# kontrol.net
KiCad netlist of a schematic drawn in EAGLE
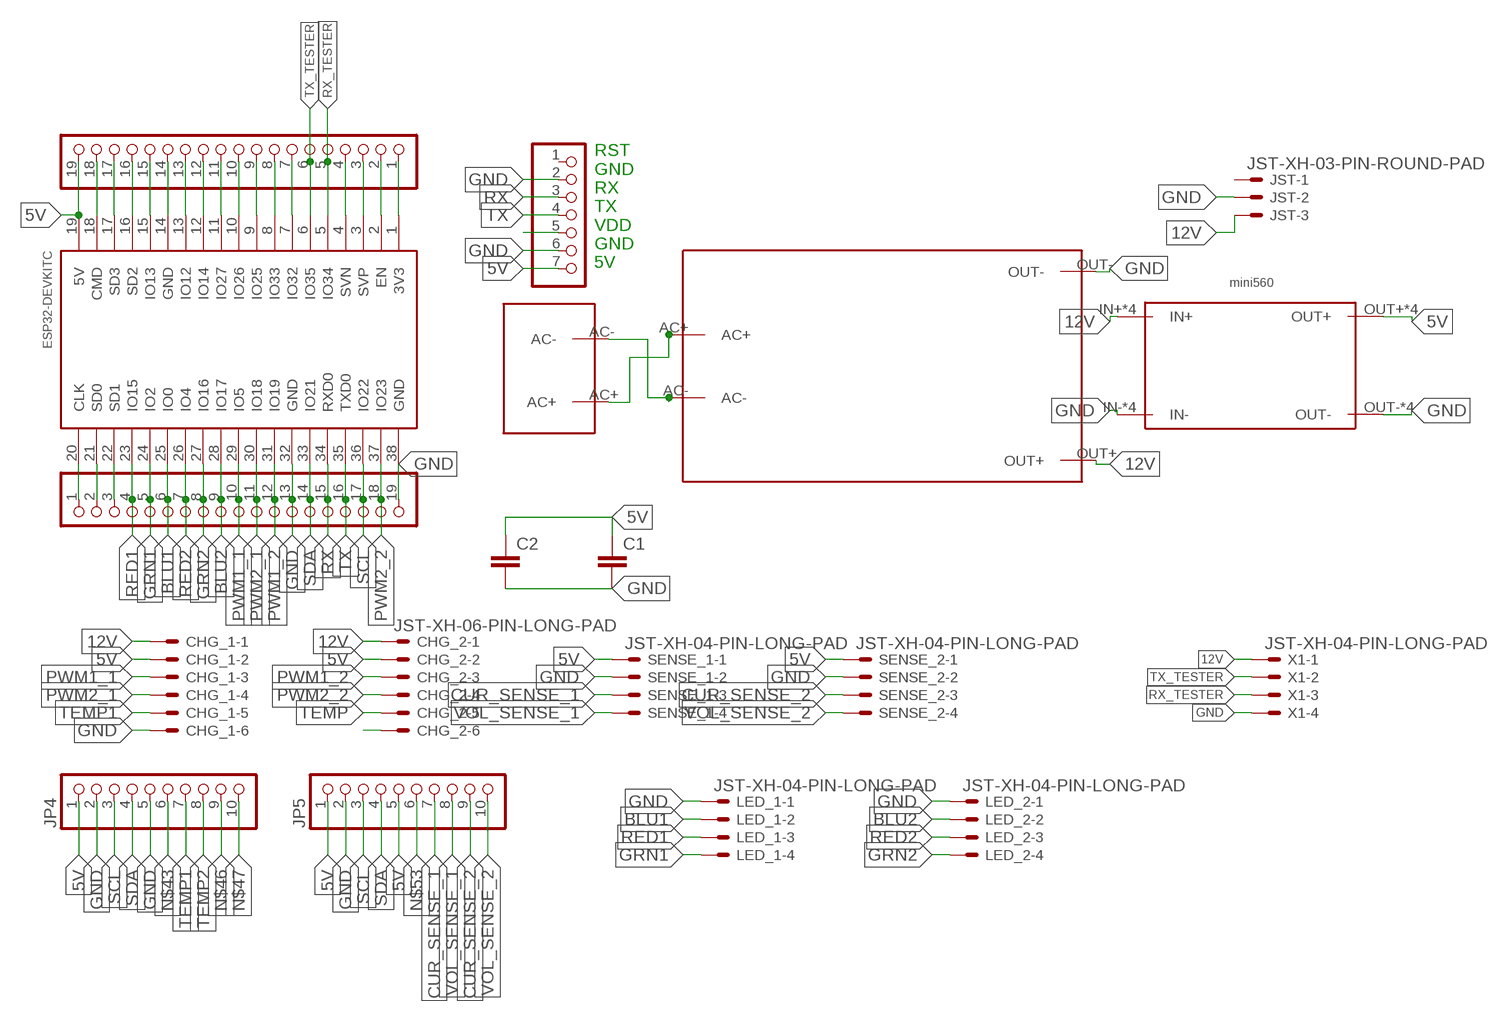
[diagram p0: schematic, sheet 1]

(export (version "E")
  (design (tool "Eeschema 10.0.6"))
  (components
    (comp (ref "AC_CONNECTOR1")
      (value "AC_CONNECTOR")
      (footprint "eagle-import:AC_CONNECTOR")
      (libsource (lib "eagle-import") (part "AC_CONNECTOR"))
    )
    (comp (ref "C1")
      (value "C2.5/5")
      (footprint "eagle-import:C2.5-5")
      (libsource (lib "eagle-import") (part "C2.5/5"))
    )
    (comp (ref "C2")
      (value "C2.5/6")
      (footprint "eagle-import:C2.5-6")
      (libsource (lib "eagle-import") (part "C2.5/6"))
    )
    (comp (ref "CHG_1")
      (value "JST-XH-06-PIN-LONG-PAD")
      (footprint "eagle-import:JST-XH-06-PACKAGE-LONG-PAD")
      (libsource (lib "eagle-import") (part "JST-XH-06-PIN-LONG-PAD"))
    )
    (comp (ref "CHG_2")
      (value "JST-XH-06-PIN-LONG-PAD")
      (footprint "eagle-import:JST-XH-06-PACKAGE-LONG-PAD")
      (libsource (lib "eagle-import") (part "JST-XH-06-PIN-LONG-PAD"))
    )
    (comp (ref "HI_LINK1")
      (value "HI_LINK")
      (footprint "eagle-import:HI_LINK")
      (libsource (lib "eagle-import") (part "HI_LINK"))
    )
    (comp (ref "JP1")
      (value "PINHD-1X7")
      (footprint "eagle-import:1X07")
      (libsource (lib "eagle-import") (part "PINHD-1X7"))
    )
    (comp (ref "JP2")
      (value "PINHD-1X19")
      (footprint "eagle-import:1X19")
      (libsource (lib "eagle-import") (part "PINHD-1X19"))
    )
    (comp (ref "JP3")
      (value "PINHD-1X19")
      (footprint "eagle-import:1X19")
      (libsource (lib "eagle-import") (part "PINHD-1X19"))
    )
    (comp (ref "JP4")
      (value "PINHD-1X10")
      (footprint "eagle-import:1X10")
      (libsource (lib "eagle-import") (part "PINHD-1X10"))
    )
    (comp (ref "JP5")
      (value "PINHD-1X10")
      (footprint "eagle-import:1X10")
      (libsource (lib "eagle-import") (part "PINHD-1X10"))
    )
    (comp (ref "JST")
      (value "JST-XH-03-PIN-ROUND-PAD")
      (footprint "eagle-import:JST-XH-03-PACKAGE-ROUND-PAD")
      (libsource (lib "eagle-import") (part "JST-XH-03-PIN-ROUND-PAD"))
    )
    (comp (ref "LED_1")
      (value "JST-XH-04-PIN-LONG-PAD")
      (footprint "eagle-import:JST-XH-04-PACKAGE-LONG-PAD")
      (libsource (lib "eagle-import") (part "JST-XH-04-PIN-LONG-PAD"))
    )
    (comp (ref "LED_2")
      (value "JST-XH-04-PIN-LONG-PAD")
      (footprint "eagle-import:JST-XH-04-PACKAGE-LONG-PAD")
      (libsource (lib "eagle-import") (part "JST-XH-04-PIN-LONG-PAD"))
    )
    (comp (ref "MINI1")
      (value "MINI560")
      (footprint "eagle-import:MINI560")
      (libsource (lib "eagle-import") (part "MINI560"))
    )
    (comp (ref "SENSE_1")
      (value "JST-XH-04-PIN-LONG-PAD")
      (footprint "eagle-import:JST-XH-04-PACKAGE-LONG-PAD")
      (libsource (lib "eagle-import") (part "JST-XH-04-PIN-LONG-PAD"))
    )
    (comp (ref "SENSE_2")
      (value "JST-XH-04-PIN-LONG-PAD")
      (footprint "eagle-import:JST-XH-04-PACKAGE-LONG-PAD")
      (libsource (lib "eagle-import") (part "JST-XH-04-PIN-LONG-PAD"))
    )
    (comp (ref "U$1")
      (value "ESP32DEVKITC")
      (footprint "eagle-import:ESP32-DEVKITC")
      (libsource (lib "eagle-import") (part "ESP32DEVKITC"))
    )
    (comp (ref "X1")
      (value "JST-XH-04-PIN-LONG-PAD")
      (footprint "eagle-import:JST-XH-04-PACKAGE-LONG-PAD")
      (libsource (lib "eagle-import") (part "Rembrandt Electronics - JST XH Connectors v1-0_JST-XH-04-PIN-LONG-PAD"))
    )
  )
  (nets
    (net (code "1") (name "5V") (class "Default")
      (node (ref "C1") (pin "1") (pinfunction "1_1") (pintype "passive"))
      (node (ref "C2") (pin "1") (pinfunction "1_1") (pintype "passive"))
      (node (ref "CHG_1") (pin "2") (pinfunction "S_2") (pintype "passive"))
      (node (ref "CHG_2") (pin "2") (pinfunction "S_2") (pintype "passive"))
      (node (ref "JP1") (pin "7") (pinfunction "7_7") (pintype "passive"))
      (node (ref "JP3") (pin "19") (pinfunction "19_19") (pintype "passive"))
      (node (ref "JP4") (pin "1") (pinfunction "1_1") (pintype "passive"))
      (node (ref "JP5") (pin "1") (pinfunction "1_1") (pintype "passive"))
      (node (ref "JP5") (pin "5") (pinfunction "5_5") (pintype "passive"))
      (node (ref "MINI1") (pin "OUT+") (pinfunction "OUT+_OUT+") (pintype "bidirectional"))
      (node (ref "MINI1") (pin "OUT+1") (pinfunction "OUT+_OUT+1") (pintype "bidirectional"))
      (node (ref "MINI1") (pin "OUT+2") (pinfunction "OUT+_OUT+2") (pintype "bidirectional"))
      (node (ref "MINI1") (pin "OUT+3") (pinfunction "OUT+_OUT+3") (pintype "bidirectional"))
      (node (ref "SENSE_1") (pin "1") (pinfunction "S_1") (pintype "passive"))
      (node (ref "SENSE_2") (pin "1") (pinfunction "S_1") (pintype "passive"))
      (node (ref "U$1") (pin "19") (pinfunction "5V_19") (pintype "bidirectional"))
    )
    (net (code "2") (name "12V") (class "Default")
      (node (ref "CHG_1") (pin "1") (pinfunction "S_1") (pintype "passive"))
      (node (ref "CHG_2") (pin "1") (pinfunction "S_1") (pintype "passive"))
      (node (ref "HI_LINK1") (pin "OUT+") (pinfunction "OUT+_OUT+") (pintype "bidirectional"))
      (node (ref "JST") (pin "3") (pinfunction "S_3") (pintype "passive"))
      (node (ref "MINI1") (pin "IN+") (pinfunction "IN+_IN+") (pintype "bidirectional"))
      (node (ref "MINI1") (pin "IN+1") (pinfunction "IN+_IN+1") (pintype "bidirectional"))
      (node (ref "MINI1") (pin "IN+2") (pinfunction "IN+_IN+2") (pintype "bidirectional"))
      (node (ref "MINI1") (pin "IN+3") (pinfunction "IN+_IN+3") (pintype "bidirectional"))
      (node (ref "X1") (pin "1") (pinfunction "S_1") (pintype "passive"))
    )
    (net (code "3") (name "BLU1") (class "Default")
      (node (ref "JP2") (pin "6") (pinfunction "6_6") (pintype "passive"))
      (node (ref "LED_1") (pin "2") (pinfunction "S_2") (pintype "passive"))
      (node (ref "U$1") (pin "25") (pinfunction "IO0_25") (pintype "bidirectional"))
    )
    (net (code "4") (name "BLU2") (class "Default")
      (node (ref "JP2") (pin "9") (pinfunction "9_9") (pintype "passive"))
      (node (ref "LED_2") (pin "2") (pinfunction "S_2") (pintype "passive"))
      (node (ref "U$1") (pin "28") (pinfunction "IO17_28") (pintype "bidirectional"))
    )
    (net (code "5") (name "CUR_SENSE_1") (class "Default")
      (node (ref "JP5") (pin "7") (pinfunction "7_7") (pintype "passive"))
      (node (ref "SENSE_1") (pin "3") (pinfunction "S_3") (pintype "passive"))
    )
    (net (code "6") (name "CUR_SENSE_2") (class "Default")
      (node (ref "JP5") (pin "9") (pinfunction "9_9") (pintype "passive"))
      (node (ref "SENSE_2") (pin "3") (pinfunction "S_3") (pintype "passive"))
    )
    (net (code "7") (name "GND") (class "Default")
      (node (ref "C1") (pin "2") (pinfunction "2_2") (pintype "passive"))
      (node (ref "C2") (pin "2") (pinfunction "2_2") (pintype "passive"))
      (node (ref "CHG_1") (pin "6") (pinfunction "S_6") (pintype "passive"))
      (node (ref "CHG_2") (pin "6") (pinfunction "S_6") (pintype "passive"))
      (node (ref "HI_LINK1") (pin "OUT-") (pinfunction "OUT-_OUT-") (pintype "bidirectional"))
      (node (ref "JP1") (pin "2") (pinfunction "2_2") (pintype "passive"))
      (node (ref "JP1") (pin "6") (pinfunction "6_6") (pintype "passive"))
      (node (ref "JP2") (pin "13") (pinfunction "13_13") (pintype "passive"))
      (node (ref "JP2") (pin "19") (pinfunction "19_19") (pintype "passive"))
      (node (ref "JP4") (pin "2") (pinfunction "2_2") (pintype "passive"))
      (node (ref "JP4") (pin "5") (pinfunction "5_5") (pintype "passive"))
      (node (ref "JP5") (pin "2") (pinfunction "2_2") (pintype "passive"))
      (node (ref "JST") (pin "2") (pinfunction "S_2") (pintype "passive"))
      (node (ref "LED_1") (pin "1") (pinfunction "S_1") (pintype "passive"))
      (node (ref "LED_2") (pin "1") (pinfunction "S_1") (pintype "passive"))
      (node (ref "MINI1") (pin "IN-") (pinfunction "IN-_IN-") (pintype "bidirectional"))
      (node (ref "MINI1") (pin "IN-1") (pinfunction "IN-_IN-1") (pintype "bidirectional"))
      (node (ref "MINI1") (pin "IN-2") (pinfunction "IN-_IN-2") (pintype "bidirectional"))
      (node (ref "MINI1") (pin "IN-3") (pinfunction "IN-_IN-3") (pintype "bidirectional"))
      (node (ref "MINI1") (pin "OUT-") (pinfunction "OUT-_OUT-") (pintype "bidirectional"))
      (node (ref "MINI1") (pin "OUT-1") (pinfunction "OUT-_OUT-1") (pintype "bidirectional"))
      (node (ref "MINI1") (pin "OUT-2") (pinfunction "OUT-_OUT-2") (pintype "bidirectional"))
      (node (ref "MINI1") (pin "OUT-3") (pinfunction "OUT-_OUT-3") (pintype "bidirectional"))
      (node (ref "SENSE_1") (pin "2") (pinfunction "S_2") (pintype "passive"))
      (node (ref "SENSE_2") (pin "2") (pinfunction "S_2") (pintype "passive"))
      (node (ref "U$1") (pin "32") (pinfunction "GND_32") (pintype "bidirectional"))
      (node (ref "U$1") (pin "38") (pinfunction "GND_38") (pintype "bidirectional"))
      (node (ref "X1") (pin "4") (pinfunction "S_4") (pintype "passive"))
    )
    (net (code "8") (name "GRN1") (class "Default")
      (node (ref "JP2") (pin "5") (pinfunction "5_5") (pintype "passive"))
      (node (ref "LED_1") (pin "4") (pinfunction "S_4") (pintype "passive"))
      (node (ref "U$1") (pin "24") (pinfunction "IO2_24") (pintype "bidirectional"))
    )
    (net (code "9") (name "GRN2") (class "Default")
      (node (ref "JP2") (pin "8") (pinfunction "8_8") (pintype "passive"))
      (node (ref "LED_2") (pin "4") (pinfunction "S_4") (pintype "passive"))
      (node (ref "U$1") (pin "27") (pinfunction "IO16_27") (pintype "bidirectional"))
    )
    (net (code "10") (name "N$43") (class "Default")
      (node (ref "JP4") (pin "6") (pinfunction "6_6") (pintype "passive"))
    )
    (net (code "11") (name "N$46") (class "Default")
      (node (ref "JP4") (pin "9") (pinfunction "9_9") (pintype "passive"))
    )
    (net (code "12") (name "N$47") (class "Default")
      (node (ref "JP4") (pin "10") (pinfunction "10_10") (pintype "passive"))
    )
    (net (code "13") (name "N$53") (class "Default")
      (node (ref "JP5") (pin "6") (pinfunction "6_6") (pintype "passive"))
    )
    (net (code "14") (name "Net-(AC_CONNECTOR1-PadAC+)") (class "Default")
      (node (ref "AC_CONNECTOR1") (pin "AC+") (pinfunction "AC+_AC+") (pintype "bidirectional"))
      (node (ref "HI_LINK1") (pin "AC+") (pinfunction "AC+_AC+") (pintype "bidirectional"))
    )
    (net (code "15") (name "Net-(AC_CONNECTOR1-PadAC-)") (class "Default")
      (node (ref "AC_CONNECTOR1") (pin "AC-") (pinfunction "AC-_AC-") (pintype "bidirectional"))
      (node (ref "HI_LINK1") (pin "AC-") (pinfunction "AC-_AC-") (pintype "bidirectional"))
    )
    (net (code "16") (name "Net-(JP3-Pad14)") (class "Default")
      (node (ref "JP3") (pin "14") (pinfunction "14_14") (pintype "passive"))
      (node (ref "U$1") (pin "14") (pinfunction "GND_14") (pintype "bidirectional"))
    )
    (net (code "17") (name "Net-(U$1-3V3)") (class "Default")
      (node (ref "JP3") (pin "1") (pinfunction "1_1") (pintype "passive"))
      (node (ref "U$1") (pin "1") (pinfunction "3V3_1") (pintype "bidirectional"))
    )
    (net (code "18") (name "Net-(U$1-CLK)") (class "Default")
      (node (ref "JP2") (pin "1") (pinfunction "1_1") (pintype "passive"))
      (node (ref "U$1") (pin "20") (pinfunction "CLK_20") (pintype "bidirectional"))
    )
    (net (code "19") (name "Net-(U$1-CMD)") (class "Default")
      (node (ref "JP3") (pin "18") (pinfunction "18_18") (pintype "passive"))
      (node (ref "U$1") (pin "18") (pinfunction "CMD_18") (pintype "bidirectional"))
    )
    (net (code "20") (name "Net-(U$1-EN)") (class "Default")
      (node (ref "JP3") (pin "2") (pinfunction "2_2") (pintype "passive"))
      (node (ref "U$1") (pin "2") (pinfunction "EN_2") (pintype "bidirectional"))
    )
    (net (code "21") (name "Net-(U$1-IO12)") (class "Default")
      (node (ref "JP3") (pin "13") (pinfunction "13_13") (pintype "passive"))
      (node (ref "U$1") (pin "13") (pinfunction "IO12_13") (pintype "bidirectional"))
    )
    (net (code "22") (name "Net-(U$1-IO13)") (class "Default")
      (node (ref "JP3") (pin "15") (pinfunction "15_15") (pintype "passive"))
      (node (ref "U$1") (pin "15") (pinfunction "IO13_15") (pintype "bidirectional"))
    )
    (net (code "23") (name "Net-(U$1-IO14)") (class "Default")
      (node (ref "JP3") (pin "12") (pinfunction "12_12") (pintype "passive"))
      (node (ref "U$1") (pin "12") (pinfunction "IO14_12") (pintype "bidirectional"))
    )
    (net (code "24") (name "Net-(U$1-IO25)") (class "Default")
      (node (ref "JP3") (pin "9") (pinfunction "9_9") (pintype "passive"))
      (node (ref "U$1") (pin "9") (pinfunction "IO25_9") (pintype "bidirectional"))
    )
    (net (code "25") (name "Net-(U$1-IO26)") (class "Default")
      (node (ref "JP3") (pin "10") (pinfunction "10_10") (pintype "passive"))
      (node (ref "U$1") (pin "10") (pinfunction "IO26_10") (pintype "bidirectional"))
    )
    (net (code "26") (name "Net-(U$1-IO27)") (class "Default")
      (node (ref "JP3") (pin "11") (pinfunction "11_11") (pintype "passive"))
      (node (ref "U$1") (pin "11") (pinfunction "IO27_11") (pintype "bidirectional"))
    )
    (net (code "27") (name "Net-(U$1-IO32)") (class "Default")
      (node (ref "JP3") (pin "7") (pinfunction "7_7") (pintype "passive"))
      (node (ref "U$1") (pin "7") (pinfunction "IO32_7") (pintype "bidirectional"))
    )
    (net (code "28") (name "Net-(U$1-IO33)") (class "Default")
      (node (ref "JP3") (pin "8") (pinfunction "8_8") (pintype "passive"))
      (node (ref "U$1") (pin "8") (pinfunction "IO33_8") (pintype "bidirectional"))
    )
    (net (code "29") (name "Net-(U$1-SD0)") (class "Default")
      (node (ref "JP2") (pin "2") (pinfunction "2_2") (pintype "passive"))
      (node (ref "U$1") (pin "21") (pinfunction "SD0_21") (pintype "bidirectional"))
    )
    (net (code "30") (name "Net-(U$1-SD1)") (class "Default")
      (node (ref "JP2") (pin "3") (pinfunction "3_3") (pintype "passive"))
      (node (ref "U$1") (pin "22") (pinfunction "SD1_22") (pintype "bidirectional"))
    )
    (net (code "31") (name "Net-(U$1-SD2)") (class "Default")
      (node (ref "JP3") (pin "16") (pinfunction "16_16") (pintype "passive"))
      (node (ref "U$1") (pin "16") (pinfunction "SD2_16") (pintype "bidirectional"))
    )
    (net (code "32") (name "Net-(U$1-SD3)") (class "Default")
      (node (ref "JP3") (pin "17") (pinfunction "17_17") (pintype "passive"))
      (node (ref "U$1") (pin "17") (pinfunction "SD3_17") (pintype "bidirectional"))
    )
    (net (code "33") (name "Net-(U$1-SVN)") (class "Default")
      (node (ref "JP3") (pin "4") (pinfunction "4_4") (pintype "passive"))
      (node (ref "U$1") (pin "4") (pinfunction "SVN_4") (pintype "bidirectional"))
    )
    (net (code "34") (name "Net-(U$1-SVP)") (class "Default")
      (node (ref "JP3") (pin "3") (pinfunction "3_3") (pintype "passive"))
      (node (ref "U$1") (pin "3") (pinfunction "SVP_3") (pintype "bidirectional"))
    )
    (net (code "35") (name "PWM1_1") (class "Default")
      (node (ref "CHG_1") (pin "3") (pinfunction "S_3") (pintype "passive"))
      (node (ref "JP2") (pin "10") (pinfunction "10_10") (pintype "passive"))
      (node (ref "U$1") (pin "29") (pinfunction "IO5_29") (pintype "bidirectional"))
    )
    (net (code "36") (name "PWM1_2") (class "Default")
      (node (ref "CHG_2") (pin "3") (pinfunction "S_3") (pintype "passive"))
      (node (ref "JP2") (pin "12") (pinfunction "12_12") (pintype "passive"))
      (node (ref "U$1") (pin "31") (pinfunction "IO19_31") (pintype "bidirectional"))
    )
    (net (code "37") (name "PWM2_1") (class "Default")
      (node (ref "CHG_1") (pin "4") (pinfunction "S_4") (pintype "passive"))
      (node (ref "JP2") (pin "11") (pinfunction "11_11") (pintype "passive"))
      (node (ref "U$1") (pin "30") (pinfunction "IO18_30") (pintype "bidirectional"))
    )
    (net (code "38") (name "PWM2_2") (class "Default")
      (node (ref "CHG_2") (pin "4") (pinfunction "S_4") (pintype "passive"))
      (node (ref "JP2") (pin "18") (pinfunction "18_18") (pintype "passive"))
      (node (ref "U$1") (pin "37") (pinfunction "IO23_37") (pintype "bidirectional"))
    )
    (net (code "39") (name "RED1") (class "Default")
      (node (ref "JP2") (pin "4") (pinfunction "4_4") (pintype "passive"))
      (node (ref "LED_1") (pin "3") (pinfunction "S_3") (pintype "passive"))
      (node (ref "U$1") (pin "23") (pinfunction "IO15_23") (pintype "bidirectional"))
    )
    (net (code "40") (name "RED2") (class "Default")
      (node (ref "JP2") (pin "7") (pinfunction "7_7") (pintype "passive"))
      (node (ref "LED_2") (pin "3") (pinfunction "S_3") (pintype "passive"))
      (node (ref "U$1") (pin "26") (pinfunction "IO4_26") (pintype "bidirectional"))
    )
    (net (code "41") (name "RX") (class "Default")
      (node (ref "JP1") (pin "3") (pinfunction "3_3") (pintype "passive"))
      (node (ref "JP2") (pin "15") (pinfunction "15_15") (pintype "passive"))
      (node (ref "U$1") (pin "34") (pinfunction "RXD0_34") (pintype "bidirectional"))
    )
    (net (code "42") (name "RX_TESTER") (class "Default")
      (node (ref "JP3") (pin "5") (pinfunction "5_5") (pintype "passive"))
      (node (ref "U$1") (pin "5") (pinfunction "IO34_5") (pintype "bidirectional"))
      (node (ref "X1") (pin "3") (pinfunction "S_3") (pintype "passive"))
    )
    (net (code "43") (name "SCL") (class "Default")
      (node (ref "JP2") (pin "17") (pinfunction "17_17") (pintype "passive"))
      (node (ref "JP4") (pin "3") (pinfunction "3_3") (pintype "passive"))
      (node (ref "JP5") (pin "3") (pinfunction "3_3") (pintype "passive"))
      (node (ref "U$1") (pin "36") (pinfunction "IO22_36") (pintype "bidirectional"))
    )
    (net (code "44") (name "SDA") (class "Default")
      (node (ref "JP2") (pin "14") (pinfunction "14_14") (pintype "passive"))
      (node (ref "JP4") (pin "4") (pinfunction "4_4") (pintype "passive"))
      (node (ref "JP5") (pin "4") (pinfunction "4_4") (pintype "passive"))
      (node (ref "U$1") (pin "33") (pinfunction "IO21_33") (pintype "bidirectional"))
    )
    (net (code "45") (name "TEMP") (class "Default")
      (node (ref "CHG_2") (pin "5") (pinfunction "S_5") (pintype "passive"))
    )
    (net (code "46") (name "TEMP1") (class "Default")
      (node (ref "CHG_1") (pin "5") (pinfunction "S_5") (pintype "passive"))
      (node (ref "JP4") (pin "7") (pinfunction "7_7") (pintype "passive"))
    )
    (net (code "47") (name "TEMP2") (class "Default")
      (node (ref "JP4") (pin "8") (pinfunction "8_8") (pintype "passive"))
    )
    (net (code "48") (name "TX") (class "Default")
      (node (ref "JP1") (pin "4") (pinfunction "4_4") (pintype "passive"))
      (node (ref "JP2") (pin "16") (pinfunction "16_16") (pintype "passive"))
      (node (ref "U$1") (pin "35") (pinfunction "TXD0_35") (pintype "bidirectional"))
    )
    (net (code "49") (name "TX_TESTER") (class "Default")
      (node (ref "JP3") (pin "6") (pinfunction "6_6") (pintype "passive"))
      (node (ref "U$1") (pin "6") (pinfunction "IO35_6") (pintype "bidirectional"))
      (node (ref "X1") (pin "2") (pinfunction "S_2") (pintype "passive"))
    )
    (net (code "50") (name "VOL_SENSE_1") (class "Default")
      (node (ref "JP5") (pin "8") (pinfunction "8_8") (pintype "passive"))
      (node (ref "SENSE_1") (pin "4") (pinfunction "S_4") (pintype "passive"))
    )
    (net (code "51") (name "VOL_SENSE_2") (class "Default")
      (node (ref "JP5") (pin "10") (pinfunction "10_10") (pintype "passive"))
      (node (ref "SENSE_2") (pin "4") (pinfunction "S_4") (pintype "passive"))
    )
    (net (code "52") (name "unconnected-(JP1-Pad1)") (class "Default")
      (node (ref "JP1") (pin "1") (pinfunction "1_1") (pintype "passive"))
    )
    (net (code "53") (name "unconnected-(JP1-Pad5)") (class "Default")
      (node (ref "JP1") (pin "5") (pinfunction "5_5") (pintype "passive"))
    )
    (net (code "54") (name "unconnected-(JSTA-S-Pad1)") (class "Default")
      (node (ref "JST") (pin "1") (pinfunction "S_1") (pintype "passive"))
    )
  )
)
